# DAC.net
KiCad netlist of a schematic drawn in Altium Designer
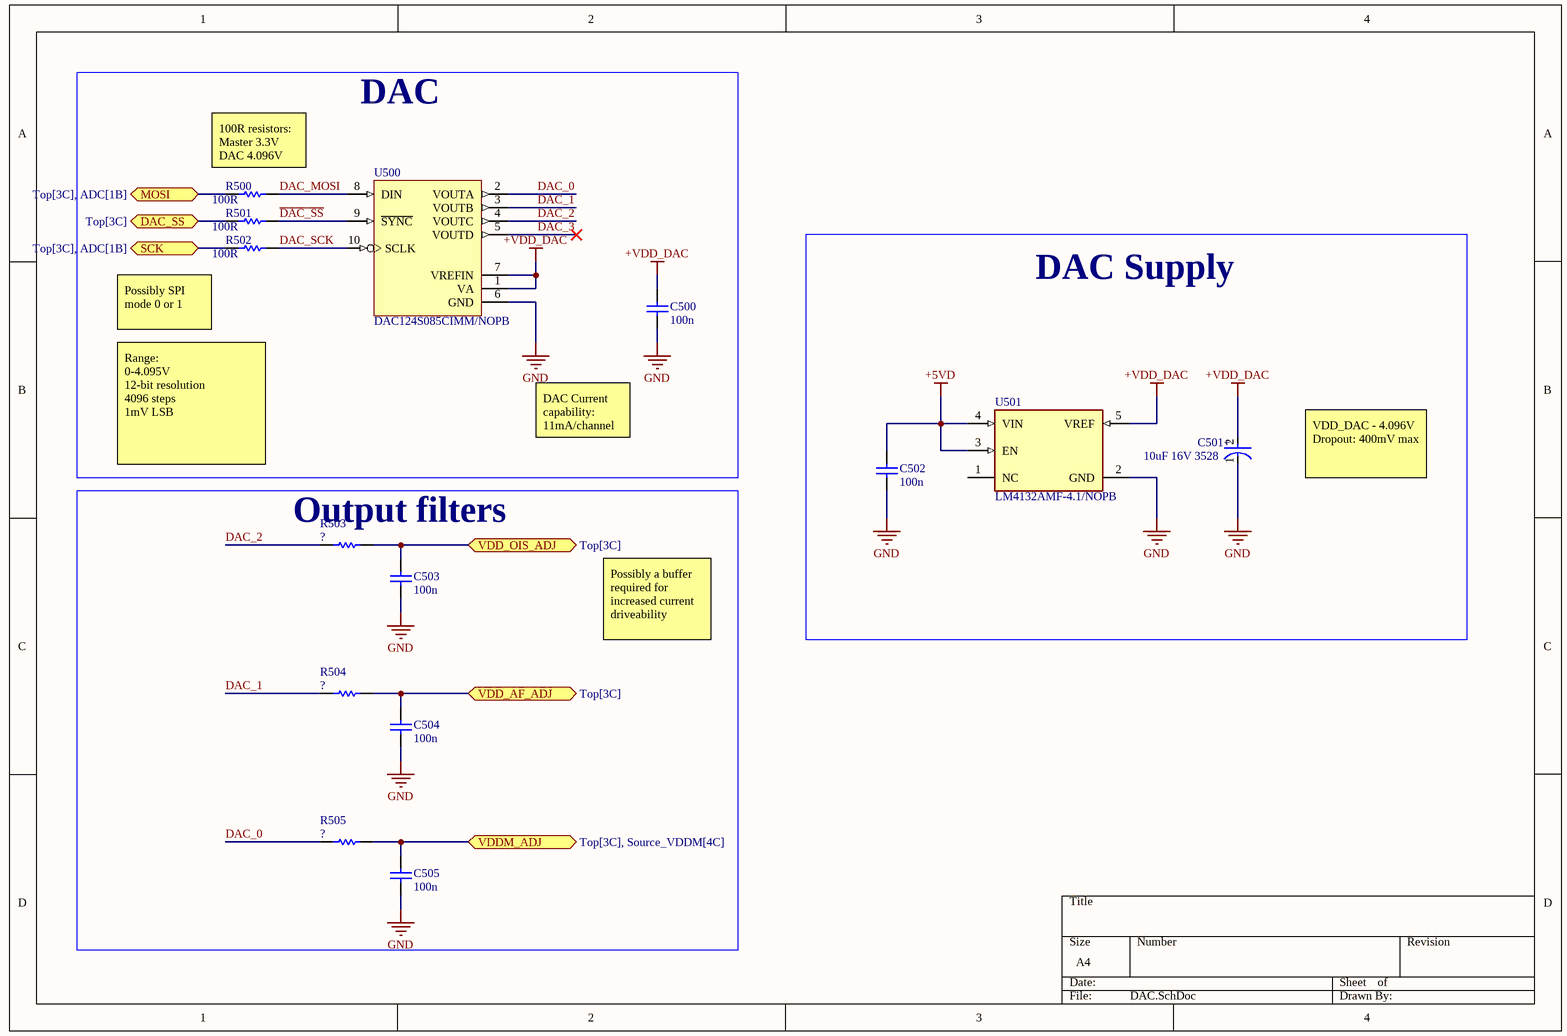
[diagram p0: DAC.SchDoc]

(export (version "E")
  (design (tool "Eeschema 10.0.6"))
  (components
    (comp (ref "C500")
      (value "100n")
      (footprint "SAMS-C0603-2_M")
      (description "Multi-layer Ceramic Capacitor, -55 to 125 degC, 2-Pin SMD (0603), RoHS, Tape and Reel")
      (fields (field (name "MANUFACTURER") "Samsung Electro-Mechanics"))
      (libsource (lib "Altium Content Vault") (part "CAP-NP-2"))
    )
    (comp (ref "C501")
      (value "10uF 16V 3528")
      (footprint "FP-T491B106K020AT-MFG")
      (description "CAP TANT 10UF 10% 20V 1411")
      (fields (field (name "TOLERANCE") "10%") (field (name "VOLTAGE") "20V"))
      (libsource (lib "Altium Content Vault") (part "a00bbbee19879c290e62620ae7e47b1"))
    )
    (comp (ref "C502")
      (value "100n")
      (footprint "SAMS-C0603-2_M")
      (description "Multi-layer Ceramic Capacitor, -55 to 125 degC, 2-Pin SMD (0603), RoHS, Tape and Reel")
      (fields (field (name "MANUFACTURER") "Samsung Electro-Mechanics"))
      (libsource (lib "Altium Content Vault") (part "CAP-NP-2"))
    )
    (comp (ref "C503")
      (value "100n")
      (footprint "SAMS-C0603-2_M")
      (description "Multi-layer Ceramic Capacitor, -55 to 125 degC, 2-Pin SMD (0603), RoHS, Tape and Reel")
      (fields (field (name "MANUFACTURER") "Samsung Electro-Mechanics"))
      (libsource (lib "Altium Content Vault") (part "CAP-NP-2"))
    )
    (comp (ref "C504")
      (value "100n")
      (footprint "SAMS-C0603-2_M")
      (description "Multi-layer Ceramic Capacitor, -55 to 125 degC, 2-Pin SMD (0603), RoHS, Tape and Reel")
      (fields (field (name "MANUFACTURER") "Samsung Electro-Mechanics"))
      (libsource (lib "Altium Content Vault") (part "CAP-NP-2"))
    )
    (comp (ref "C505")
      (value "100n")
      (footprint "SAMS-C0603-2_M")
      (description "Multi-layer Ceramic Capacitor, -55 to 125 degC, 2-Pin SMD (0603), RoHS, Tape and Reel")
      (fields (field (name "MANUFACTURER") "Samsung Electro-Mechanics"))
      (libsource (lib "Altium Content Vault") (part "CAP-NP-2"))
    )
    (comp (ref "R500")
      (value "100R")
      (footprint "RESC1608X55X30ML15T15")
      (fields (field (name "MANUFACTURER") "Panasonic") (field (name "PART NUMBER") "ERJ-3EKF1000V"))
      (libsource (lib "Altium Content Vault") (part "RES"))
    )
    (comp (ref "R501")
      (value "100R")
      (footprint "RESC1608X55X30ML15T15")
      (fields (field (name "MANUFACTURER") "Panasonic") (field (name "PART NUMBER") "ERJ-3EKF1000V"))
      (libsource (lib "Altium Content Vault") (part "RES"))
    )
    (comp (ref "R502")
      (value "100R")
      (footprint "RESC1608X55X30ML15T15")
      (fields (field (name "MANUFACTURER") "Panasonic") (field (name "PART NUMBER") "ERJ-3EKF1000V"))
      (libsource (lib "Altium Content Vault") (part "RES"))
    )
    (comp (ref "R503")
      (value "?")
      (footprint "RESC1608X55X30ML15T15")
      (fields (field (name "MANUFACTURER") "Panasonic") (field (name "PART NUMBER") "ERJ-3EKF1000V"))
      (libsource (lib "Altium Content Vault") (part "RES"))
    )
    (comp (ref "R504")
      (value "?")
      (footprint "RESC1608X55X30ML15T15")
      (fields (field (name "MANUFACTURER") "Panasonic") (field (name "PART NUMBER") "ERJ-3EKF1000V"))
      (libsource (lib "Altium Content Vault") (part "RES"))
    )
    (comp (ref "R505")
      (value "?")
      (footprint "RESC1608X55X30ML15T15")
      (fields (field (name "MANUFACTURER") "Panasonic") (field (name "PART NUMBER") "ERJ-3EKF1000V"))
      (libsource (lib "Altium Content Vault") (part "RES"))
    )
    (comp (ref "U500")
      (value "DAC124S085CIMM/NOPB")
      (footprint "MUB10A_L")
      (fields (field (name "MANUFACTURER") "National Semiconductor"))
      (libsource (lib "Altium Content Vault") (part "CON-DAC-DAC124S085-10"))
    )
    (comp (ref "U501")
      (value "LM4132AMF-4.1/NOPB")
      (footprint "FP-DBV0005A-IPC_C")
      (description "IC VREF SERIES 0.05% SOT23-5")
      (fields (field (name "TOLERANCE") "0.05%"))
      (libsource (lib "Altium Content Vault") (part "b0e85eef8db41206fd3047e42215f36"))
    )
  )
  (nets
    (net (code "1") (name "+5VD") (class "Default")
      (node (ref "C502") (pin "2") (pinfunction "2_2") (pintype "passive"))
      (node (ref "U501") (pin "3") (pinfunction "EN_3") (pintype "input"))
      (node (ref "U501") (pin "4") (pinfunction "VIN_4") (pintype "input"))
    )
    (net (code "2") (name "+VDD_DAC") (class "Default")
      (node (ref "C500") (pin "2") (pinfunction "2_2") (pintype "passive"))
      (node (ref "C501") (pin "2") (pinfunction "A_2") (pintype "passive"))
      (node (ref "U500") (pin "1") (pinfunction "VA_1") (pintype "power_in"))
      (node (ref "U500") (pin "7") (pinfunction "VREFIN_7") (pintype "power_in"))
      (node (ref "U501") (pin "5") (pinfunction "VREF_5") (pintype "input"))
    )
    (net (code "3") (name "/DAC_0") (class "Default")
      (node (ref "R505") (pin "1") (pinfunction "1_1") (pintype "passive"))
      (node (ref "U500") (pin "2") (pinfunction "VOUTA_2") (pintype "output"))
    )
    (net (code "4") (name "/DAC_1") (class "Default")
      (node (ref "R504") (pin "1") (pinfunction "1_1") (pintype "passive"))
      (node (ref "U500") (pin "3") (pinfunction "VOUTB_3") (pintype "output"))
    )
    (net (code "5") (name "/DAC_2") (class "Default")
      (node (ref "R503") (pin "1") (pinfunction "1_1") (pintype "passive"))
      (node (ref "U500") (pin "4") (pinfunction "VOUTC_4") (pintype "output"))
    )
    (net (code "6") (name "/DAC_3") (class "Default")
      (node (ref "U500") (pin "5") (pinfunction "VOUTD_5") (pintype "output+no_connect"))
    )
    (net (code "7") (name "/DAC_MOSI") (class "Default")
      (node (ref "R500") (pin "2") (pinfunction "2_2") (pintype "passive"))
      (node (ref "U500") (pin "8") (pinfunction "DIN_8") (pintype "input"))
    )
    (net (code "8") (name "/DAC_SCK") (class "Default")
      (node (ref "R502") (pin "2") (pinfunction "2_2") (pintype "passive"))
      (node (ref "U500") (pin "10") (pinfunction "SCLK_10") (pintype "input"))
    )
    (net (code "9") (name "/DAC_SS") (class "Default")
      (node (ref "R501") (pin "1") (pinfunction "1_1") (pintype "passive"))
    )
    (net (code "10") (name "/MOSI") (class "Default")
      (node (ref "R500") (pin "1") (pinfunction "1_1") (pintype "passive"))
    )
    (net (code "11") (name "/SCK") (class "Default")
      (node (ref "R502") (pin "1") (pinfunction "1_1") (pintype "passive"))
    )
    (net (code "12") (name "/VDDM_ADJ") (class "Default")
      (node (ref "C505") (pin "2") (pinfunction "2_2") (pintype "passive"))
      (node (ref "R505") (pin "2") (pinfunction "2_2") (pintype "passive"))
    )
    (net (code "13") (name "/VDD_AF_ADJ") (class "Default")
      (node (ref "C504") (pin "2") (pinfunction "2_2") (pintype "passive"))
      (node (ref "R504") (pin "2") (pinfunction "2_2") (pintype "passive"))
    )
    (net (code "14") (name "/VDD_OIS_ADJ") (class "Default")
      (node (ref "C503") (pin "2") (pinfunction "2_2") (pintype "passive"))
      (node (ref "R503") (pin "2") (pinfunction "2_2") (pintype "passive"))
    )
    (net (code "15") (name "/~{DAC_SS}") (class "Default")
      (node (ref "R501") (pin "2") (pinfunction "2_2") (pintype "passive"))
      (node (ref "U500") (pin "9") (pinfunction "~{SYNC}_9") (pintype "input"))
    )
    (net (code "16") (name "GND") (class "Default")
      (node (ref "C500") (pin "1") (pinfunction "1_1") (pintype "passive"))
      (node (ref "C501") (pin "1") (pinfunction "C_1") (pintype "passive"))
      (node (ref "C502") (pin "1") (pinfunction "1_1") (pintype "passive"))
      (node (ref "C503") (pin "1") (pinfunction "1_1") (pintype "passive"))
      (node (ref "C504") (pin "1") (pinfunction "1_1") (pintype "passive"))
      (node (ref "C505") (pin "1") (pinfunction "1_1") (pintype "passive"))
      (node (ref "U500") (pin "6") (pinfunction "GND_6") (pintype "power_in"))
      (node (ref "U501") (pin "2") (pinfunction "GND_2") (pintype "power_in"))
    )
    (net (code "17") (name "unconnected-(U501-NC-Pad1)") (class "Default")
      (node (ref "U501") (pin "1") (pinfunction "NC_1") (pintype "passive"))
    )
  )
)
